# Power_-_MGT1V2.net
KiCad netlist of a schematic drawn in Altium Designer
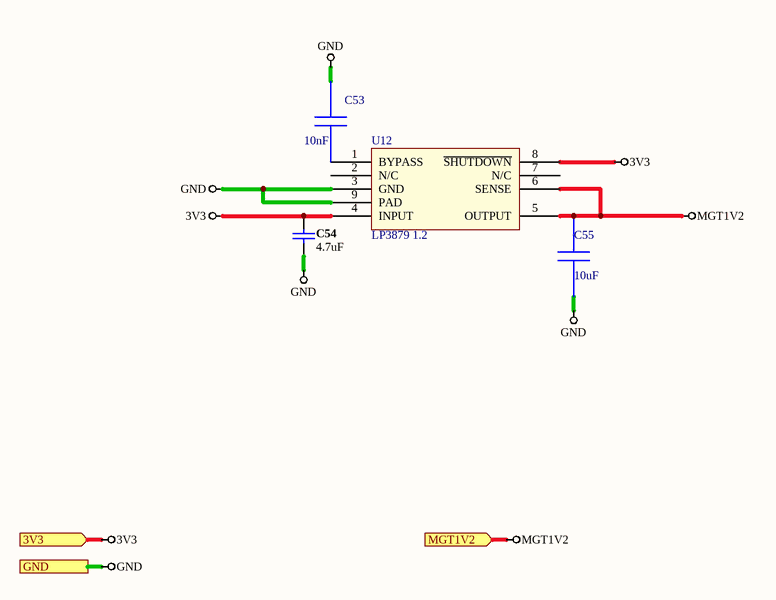
[diagram p0: Power - MGT1V2.SchDoc]

(export (version "E")
  (design (tool "Eeschema 10.0.6"))
  (components
    (comp (ref "C53")
      (value "10nF")
      (footprint "CAPC0402(1005)60_L")
      (description "GRM155R71E103KA0")
      (fields (field (name "MANUFACTURER PART NUMBER") "GRM155R71E103KA01D"))
      (libsource (lib "TI WEBENCH") (part "Ccp"))
    )
    (comp (ref "C54")
      (value "4.7uF")
      (footprint "CAPC0603(1608)55_L")
      (fields
        (field (name "TOLERANCE") "±10%")
        (field (name "MANUFACTURER PART NUMBER") "CC0603KRX5R6BB475")
        (field (name "Comment") "CAP 4.7uF 10V 0603(1608)")
      )
      (libsource (lib "Component_Database") (part "CAP_NP"))
    )
    (comp (ref "C55")
      (value "10uF")
      (footprint "1206")
      (description "GRM31CR61E106KA1")
      (fields (field (name "MANUFACTURER PART NUMBER") "GRM31CR61E106KA12L"))
      (libsource (lib "TI WEBENCH") (part "Cin"))
    )
    (comp (ref "U12") (value "LP3879 1.2") (footprint "MRA08A") (libsource (lib "Power") (part "LP3879")))
  )
  (nets
    (net (code "1") (name "3V3") (class "Default")
      (node (ref "C54") (pin "2") (pinfunction "2_2") (pintype "passive"))
      (node (ref "U12") (pin "4") (pinfunction "INPUT_4") (pintype "passive"))
      (node (ref "U12") (pin "8") (pinfunction "~{SHUTDOWN}_8") (pintype "passive"))
    )
    (net (code "2") (name "GND") (class "Default")
      (node (ref "C53") (pin "1") (pinfunction "1_1") (pintype "passive"))
      (node (ref "C54") (pin "1") (pinfunction "1_1") (pintype "passive"))
      (node (ref "C55") (pin "2") (pinfunction "2_2") (pintype "passive"))
      (node (ref "U12") (pin "3") (pinfunction "GND_3") (pintype "passive"))
      (node (ref "U12") (pin "9") (pinfunction "PAD_9") (pintype "passive"))
    )
    (net (code "3") (name "MGT1V2") (class "Default")
      (node (ref "C55") (pin "1") (pinfunction "1_1") (pintype "passive"))
      (node (ref "U12") (pin "5") (pinfunction "OUTPUT_5") (pintype "passive"))
      (node (ref "U12") (pin "6") (pinfunction "SENSE_6") (pintype "passive"))
    )
    (net (code "4") (name "Net-(U12-BYPASS)") (class "Default")
      (node (ref "C53") (pin "2") (pinfunction "2_2") (pintype "passive"))
      (node (ref "U12") (pin "1") (pinfunction "BYPASS_1") (pintype "passive"))
    )
    (net (code "5") (name "unconnected-(U12-N{slash}C-Pad2)") (class "Default")
      (node (ref "U12") (pin "2") (pinfunction "N/C_2") (pintype "passive"))
    )
    (net (code "6") (name "unconnected-(U12-N{slash}C-Pad7)") (class "Default")
      (node (ref "U12") (pin "7") (pinfunction "N/C_7") (pintype "passive"))
    )
  )
)
